# SensorBoard.net
KiCad netlist of a schematic drawn in EAGLE
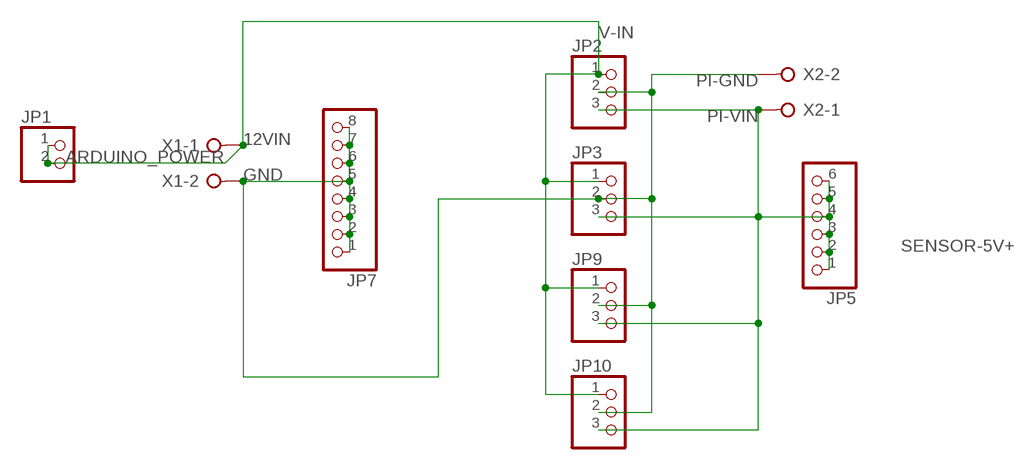
[diagram p0: schematic, sheet 1]

(export (version "E")
  (design (tool "Eeschema 10.0.6"))
  (components
    (comp (ref "JP1")
      (value "PINHD-1X2")
      (footprint "eagle-import:1X02")
      (libsource (lib "eagle-import") (part "PINHD-1X2"))
    )
    (comp (ref "JP2")
      (value "PINHD-1X3")
      (footprint "eagle-import:1X03")
      (libsource (lib "eagle-import") (part "PINHD-1X3"))
    )
    (comp (ref "JP3")
      (value "PINHD-1X3")
      (footprint "eagle-import:1X03")
      (libsource (lib "eagle-import") (part "PINHD-1X3"))
    )
    (comp (ref "JP5")
      (value "PINHD-1X6")
      (footprint "eagle-import:1X06")
      (libsource (lib "eagle-import") (part "PINHD-1X6"))
    )
    (comp (ref "JP7")
      (value "PINHD-1X8")
      (footprint "eagle-import:1X08")
      (libsource (lib "eagle-import") (part "PINHD-1X8"))
    )
    (comp (ref "JP9")
      (value "PINHD-1X3")
      (footprint "eagle-import:1X03")
      (libsource (lib "eagle-import") (part "PINHD-1X3"))
    )
    (comp (ref "JP10")
      (value "PINHD-1X3")
      (footprint "eagle-import:1X03")
      (libsource (lib "eagle-import") (part "PINHD-1X3"))
    )
    (comp (ref "X1")
      (value "W237-02P")
      (footprint "eagle-import:W237-132")
      (libsource (lib "eagle-import") (part "W237-02P"))
    )
    (comp (ref "X2")
      (value "W237-02P")
      (footprint "eagle-import:W237-132")
      (libsource (lib "eagle-import") (part "W237-02P"))
    )
  )
  (nets
    (net (code "1") (name "/SENSOR-5V+") (class "Default")
      (node (ref "JP10") (pin "3") (pinfunction "3_3") (pintype "passive"))
      (node (ref "JP2") (pin "3") (pinfunction "3_3") (pintype "passive"))
      (node (ref "JP3") (pin "3") (pinfunction "3_3") (pintype "passive"))
      (node (ref "JP5") (pin "1") (pinfunction "1_1") (pintype "passive"))
      (node (ref "JP5") (pin "2") (pinfunction "2_2") (pintype "passive"))
      (node (ref "JP5") (pin "3") (pinfunction "3_3") (pintype "passive"))
      (node (ref "JP5") (pin "4") (pinfunction "4_4") (pintype "passive"))
      (node (ref "JP5") (pin "5") (pinfunction "5_5") (pintype "passive"))
      (node (ref "JP5") (pin "6") (pinfunction "6_6") (pintype "passive"))
      (node (ref "JP9") (pin "3") (pinfunction "3_3") (pintype "passive"))
      (node (ref "X2") (pin "1") (pinfunction "KL_1") (pintype "passive"))
    )
    (net (code "2") (name "/V-IN") (class "Default")
      (node (ref "JP1") (pin "1") (pinfunction "1_1") (pintype "passive"))
      (node (ref "JP1") (pin "2") (pinfunction "2_2") (pintype "passive"))
      (node (ref "JP10") (pin "1") (pinfunction "1_1") (pintype "passive"))
      (node (ref "JP2") (pin "1") (pinfunction "1_1") (pintype "passive"))
      (node (ref "JP3") (pin "1") (pinfunction "1_1") (pintype "passive"))
      (node (ref "JP9") (pin "1") (pinfunction "1_1") (pintype "passive"))
      (node (ref "X1") (pin "1") (pinfunction "KL_1") (pintype "passive"))
    )
    (net (code "3") (name "Net-(X1B-KL)") (class "Default")
      (node (ref "JP10") (pin "2") (pinfunction "2_2") (pintype "passive"))
      (node (ref "JP2") (pin "2") (pinfunction "2_2") (pintype "passive"))
      (node (ref "JP3") (pin "2") (pinfunction "2_2") (pintype "passive"))
      (node (ref "JP7") (pin "1") (pinfunction "1_1") (pintype "passive"))
      (node (ref "JP7") (pin "2") (pinfunction "2_2") (pintype "passive"))
      (node (ref "JP7") (pin "3") (pinfunction "3_3") (pintype "passive"))
      (node (ref "JP7") (pin "4") (pinfunction "4_4") (pintype "passive"))
      (node (ref "JP7") (pin "5") (pinfunction "5_5") (pintype "passive"))
      (node (ref "JP7") (pin "6") (pinfunction "6_6") (pintype "passive"))
      (node (ref "JP7") (pin "7") (pinfunction "7_7") (pintype "passive"))
      (node (ref "JP7") (pin "8") (pinfunction "8_8") (pintype "passive"))
      (node (ref "JP9") (pin "2") (pinfunction "2_2") (pintype "passive"))
      (node (ref "X1") (pin "2") (pinfunction "KL_2") (pintype "passive"))
      (node (ref "X2") (pin "2") (pinfunction "KL_2") (pintype "passive"))
    )
  )
)
